# battery-select.net
KiCad netlist of a schematic drawn in Altium Designer
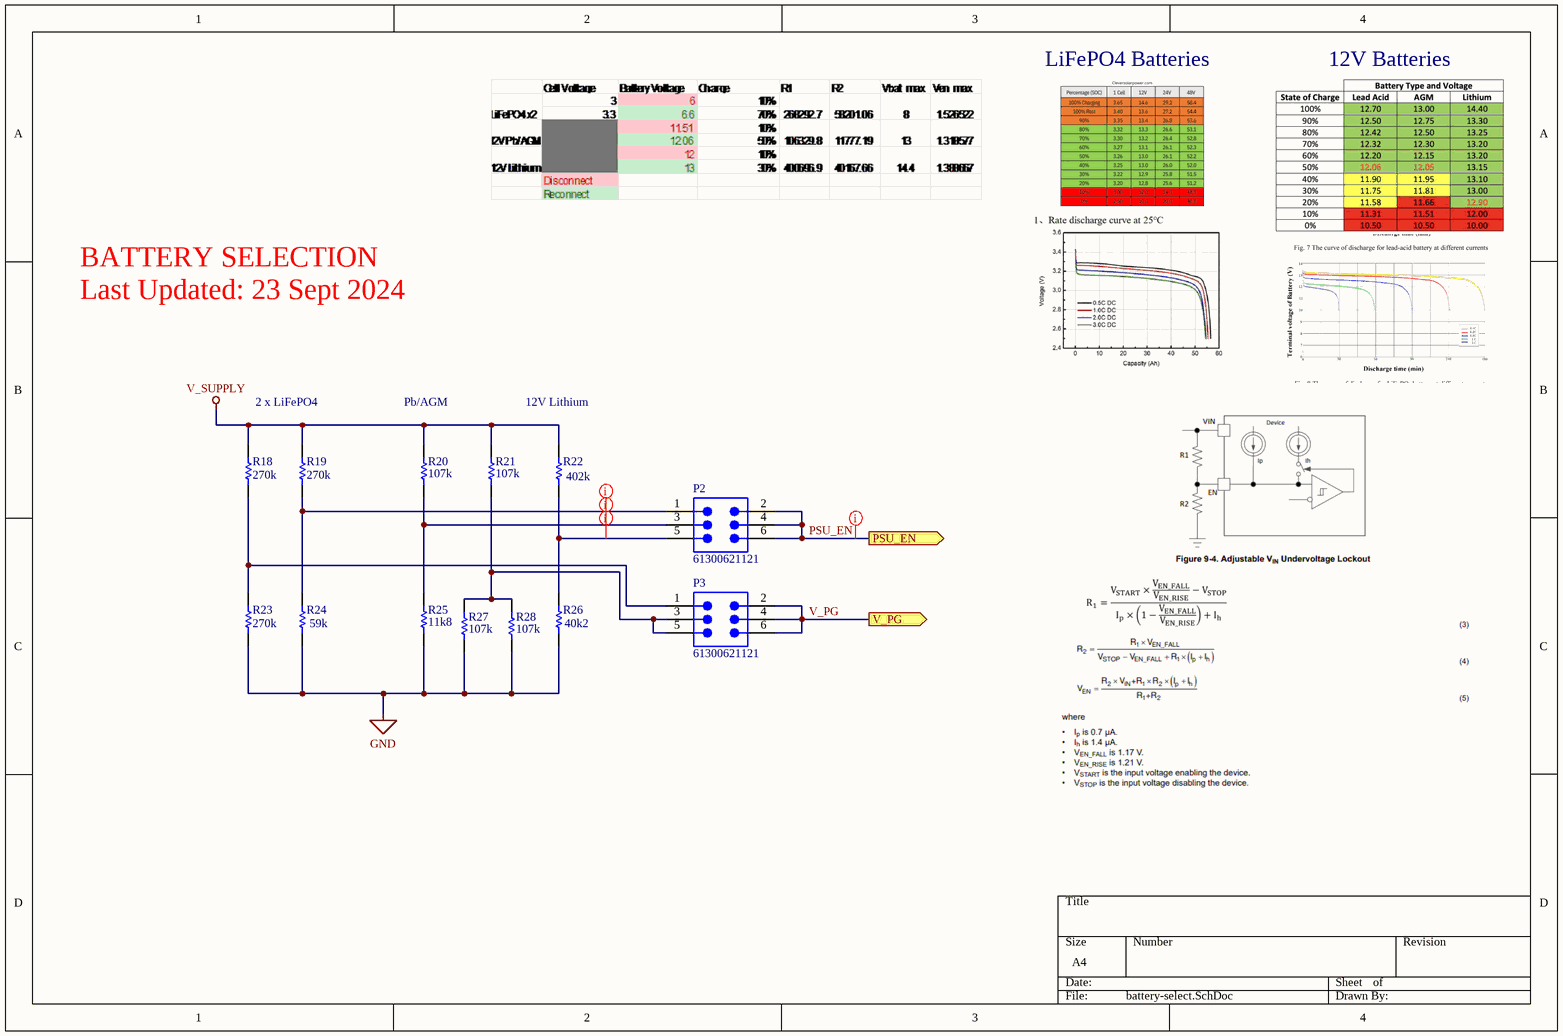
[diagram p0: battery-select.SchDoc]

(export (version "E")
  (design (tool "Eeschema 10.0.6"))
  (components
    (comp (ref "P2")
      (value "61300621121")
      (footprint "61300621121")
      (libsource (lib "Camosun College") (part "Header_Male_2R_06P"))
    )
    (comp (ref "P3")
      (value "61300621121")
      (footprint "61300621121")
      (libsource (lib "Camosun College") (part "Header_Male_2R_06P"))
    )
    (comp (ref "R18")
      (value "270k")
      (footprint "RESC2013X70X40LL20T20")
      (fields (field (name "PART NUMBER") "ERJ6ENF2703V") (field (name "MANUFACTURER") "Panasonic"))
      (libsource (lib "Altium Content Vault") (part "RES"))
    )
    (comp (ref "R19")
      (value "270k")
      (footprint "RESC2013X70X40LL20T20")
      (fields (field (name "PART NUMBER") "ERJ6ENF2703V") (field (name "MANUFACTURER") "Panasonic"))
      (libsource (lib "Altium Content Vault") (part "RES"))
    )
    (comp (ref "R20")
      (value "107k")
      (footprint "RESC2013X70X40LL20T20")
      (fields (field (name "MANUFACTURER") "Panasonic") (field (name "PART NUMBER") "ERJ-6ENF1073V"))
      (libsource (lib "Altium Content Vault") (part "RES"))
    )
    (comp (ref "R21")
      (value "107k")
      (footprint "RESC2013X70X40LL20T20")
      (fields (field (name "MANUFACTURER") "Panasonic") (field (name "PART NUMBER") "ERJ-6ENF1073V"))
      (libsource (lib "Altium Content Vault") (part "RES"))
    )
    (comp (ref "R22")
      (value "402k")
      (footprint "RESC2013X70X40LL20T20")
      (fields (field (name "PART NUMBER") "ERJ-6ENF4023V") (field (name "MANUFACTURER") "Panasonic"))
      (libsource (lib "Altium Content Vault") (part "RES"))
    )
    (comp (ref "R23")
      (value "270k")
      (footprint "RESC2013X70X40LL20T20")
      (fields (field (name "PART NUMBER") "ERJ6ENF2703V") (field (name "MANUFACTURER") "Panasonic"))
      (libsource (lib "Altium Content Vault") (part "RES"))
    )
    (comp (ref "R24")
      (value "59k")
      (footprint "RESC2013X70X40LL20T20")
      (fields (field (name "MANUFACTURER") "Panasonic") (field (name "PART NUMBER") "ERJ-6ENF5902V"))
      (libsource (lib "Altium Content Vault") (part "RES"))
    )
    (comp (ref "R25")
      (value "11k8")
      (footprint "RESC2013X70X40LL20T20")
      (fields (field (name "PART NUMBER") "ERJ-6ENF1182V") (field (name "MANUFACTURER") "Panasonic"))
      (libsource (lib "Altium Content Vault") (part "RES"))
    )
    (comp (ref "R26")
      (value "40k2")
      (footprint "RESC2013X70X40LL20T20")
      (fields (field (name "MANUFACTURER") "Panasonic") (field (name "PART NUMBER") "ERJ-6ENF4022V"))
      (libsource (lib "Altium Content Vault") (part "RES"))
    )
    (comp (ref "R27")
      (value "107k")
      (footprint "RESC2013X70X40LL20T20")
      (fields (field (name "MANUFACTURER") "Panasonic") (field (name "PART NUMBER") "ERJ-6ENF1073V"))
      (libsource (lib "Altium Content Vault") (part "RES"))
    )
    (comp (ref "R28")
      (value "107k")
      (footprint "RESC2013X70X40LL20T20")
      (fields (field (name "MANUFACTURER") "Panasonic") (field (name "PART NUMBER") "ERJ-6ENF1073V"))
      (libsource (lib "Altium Content Vault") (part "RES"))
    )
  )
  (nets
    (net (code "1") (name "/PSU_EN") (class "Default")
      (node (ref "P2") (pin "2") (pinfunction "2_2") (pintype "passive"))
      (node (ref "P2") (pin "4") (pinfunction "4_4") (pintype "passive"))
      (node (ref "P2") (pin "6") (pinfunction "6_6") (pintype "passive"))
    )
    (net (code "2") (name "/V_PG") (class "Default")
      (node (ref "P3") (pin "2") (pinfunction "2_2") (pintype "passive"))
      (node (ref "P3") (pin "4") (pinfunction "4_4") (pintype "passive"))
      (node (ref "P3") (pin "6") (pinfunction "6_6") (pintype "passive"))
    )
    (net (code "3") (name "GND") (class "Default")
      (node (ref "R23") (pin "1") (pinfunction "1_1") (pintype "passive"))
      (node (ref "R24") (pin "1") (pinfunction "1_1") (pintype "passive"))
      (node (ref "R25") (pin "1") (pinfunction "1_1") (pintype "passive"))
      (node (ref "R26") (pin "1") (pinfunction "1_1") (pintype "passive"))
      (node (ref "R27") (pin "1") (pinfunction "1_1") (pintype "passive"))
      (node (ref "R28") (pin "1") (pinfunction "1_1") (pintype "passive"))
    )
    (net (code "4") (name "Net-(P2-Pad1)") (class "Default")
      (node (ref "P2") (pin "1") (pinfunction "1_1") (pintype "passive"))
      (node (ref "R19") (pin "1") (pinfunction "1_1") (pintype "passive"))
      (node (ref "R24") (pin "2") (pinfunction "2_2") (pintype "passive"))
    )
    (net (code "5") (name "Net-(P2-Pad3)") (class "Default")
      (node (ref "P2") (pin "3") (pinfunction "3_3") (pintype "passive"))
      (node (ref "R20") (pin "1") (pinfunction "1_1") (pintype "passive"))
      (node (ref "R25") (pin "2") (pinfunction "2_2") (pintype "passive"))
    )
    (net (code "6") (name "Net-(P2-Pad5)") (class "Default")
      (node (ref "P2") (pin "5") (pinfunction "5_5") (pintype "passive"))
      (node (ref "R22") (pin "1") (pinfunction "1_1") (pintype "passive"))
      (node (ref "R26") (pin "2") (pinfunction "2_2") (pintype "passive"))
    )
    (net (code "7") (name "Net-(P3-Pad1)") (class "Default")
      (node (ref "P3") (pin "1") (pinfunction "1_1") (pintype "passive"))
      (node (ref "R18") (pin "1") (pinfunction "1_1") (pintype "passive"))
      (node (ref "R23") (pin "2") (pinfunction "2_2") (pintype "passive"))
    )
    (net (code "8") (name "Net-(P3-Pad3)") (class "Default")
      (node (ref "P3") (pin "3") (pinfunction "3_3") (pintype "passive"))
      (node (ref "P3") (pin "5") (pinfunction "5_5") (pintype "passive"))
      (node (ref "R21") (pin "1") (pinfunction "1_1") (pintype "passive"))
      (node (ref "R27") (pin "2") (pinfunction "2_2") (pintype "passive"))
      (node (ref "R28") (pin "2") (pinfunction "2_2") (pintype "passive"))
    )
    (net (code "9") (name "V_SUPPLY") (class "Default")
      (node (ref "R18") (pin "2") (pinfunction "2_2") (pintype "passive"))
      (node (ref "R19") (pin "2") (pinfunction "2_2") (pintype "passive"))
      (node (ref "R20") (pin "2") (pinfunction "2_2") (pintype "passive"))
      (node (ref "R21") (pin "2") (pinfunction "2_2") (pintype "passive"))
      (node (ref "R22") (pin "2") (pinfunction "2_2") (pintype "passive"))
    )
  )
)
